# N-P-MOSFET_adapter.net
KiCad netlist of a schematic drawn in EAGLE
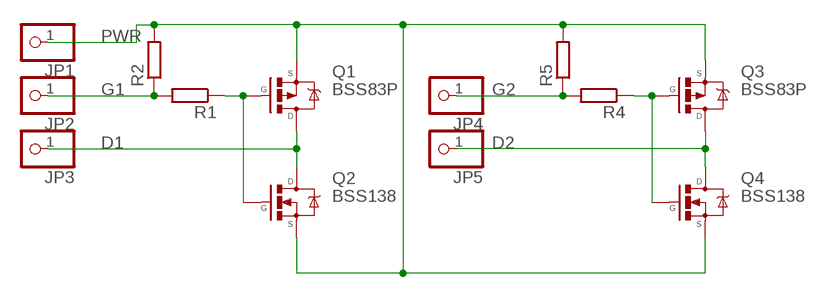
[diagram p0: schematic, sheet 1]

(export (version "E")
  (design (tool "Eeschema 10.0.6"))
  (components
    (comp (ref "JP1")
      (value "PINHD-1X1JUST_PIN")
      (footprint "eagle-import:1X01_BARE")
      (libsource (lib "eagle-import") (part "PINHD-1X1JUST_PIN"))
    )
    (comp (ref "JP2")
      (value "PINHD-1X1JUST_PIN")
      (footprint "eagle-import:1X01_BARE")
      (libsource (lib "eagle-import") (part "PINHD-1X1JUST_PIN"))
    )
    (comp (ref "JP3")
      (value "PINHD-1X1JUST_PIN")
      (footprint "eagle-import:1X01_BARE")
      (libsource (lib "eagle-import") (part "PINHD-1X1JUST_PIN"))
    )
    (comp (ref "JP4")
      (value "PINHD-1X1JUST_PIN")
      (footprint "eagle-import:1X01_BARE")
      (libsource (lib "eagle-import") (part "PINHD-1X1JUST_PIN"))
    )
    (comp (ref "JP5")
      (value "PINHD-1X1JUST_PIN")
      (footprint "eagle-import:1X01_BARE")
      (libsource (lib "eagle-import") (part "PINHD-1X1JUST_PIN"))
    )
    (comp (ref "Q1")
      (value "BSS83P")
      (footprint "eagle-import:SOT23")
      (libsource (lib "eagle-import") (part "BSS83P"))
    )
    (comp (ref "Q2")
      (value "BSS138")
      (footprint "eagle-import:SOT23")
      (libsource (lib "eagle-import") (part "BSS138"))
    )
    (comp (ref "Q3")
      (value "BSS83P")
      (footprint "eagle-import:SOT23")
      (libsource (lib "eagle-import") (part "BSS83P"))
    )
    (comp (ref "Q4")
      (value "BSS138")
      (footprint "eagle-import:SOT23")
      (libsource (lib "eagle-import") (part "BSS138"))
    )
    (comp (ref "R1")
      (value "R-EU_R0805")
      (footprint "eagle-import:R0805")
      (libsource (lib "eagle-import") (part "R-EU_R0805"))
    )
    (comp (ref "R2")
      (value "R-EU_R0805")
      (footprint "eagle-import:R0805")
      (libsource (lib "eagle-import") (part "R-EU_R0805"))
    )
    (comp (ref "R4")
      (value "R-EU_R0805")
      (footprint "eagle-import:R0805")
      (libsource (lib "eagle-import") (part "R-EU_R0805"))
    )
    (comp (ref "R5")
      (value "R-EU_R0805")
      (footprint "eagle-import:R0805")
      (libsource (lib "eagle-import") (part "R-EU_R0805"))
    )
  )
  (nets
    (net (code "1") (name "/D1") (class "Default")
      (node (ref "JP3") (pin "1") (pinfunction "1_1") (pintype "passive"))
      (node (ref "Q1") (pin "3") (pinfunction "D_3") (pintype "passive"))
      (node (ref "Q2") (pin "3") (pinfunction "D_3") (pintype "passive"))
    )
    (net (code "2") (name "/D2") (class "Default")
      (node (ref "JP5") (pin "1") (pinfunction "1_1") (pintype "passive"))
      (node (ref "Q3") (pin "3") (pinfunction "D_3") (pintype "passive"))
      (node (ref "Q4") (pin "3") (pinfunction "D_3") (pintype "passive"))
    )
    (net (code "3") (name "/G1") (class "Default")
      (node (ref "JP2") (pin "1") (pinfunction "1_1") (pintype "passive"))
      (node (ref "R1") (pin "2") (pinfunction "2_2") (pintype "passive"))
      (node (ref "R2") (pin "1") (pinfunction "1_1") (pintype "passive"))
    )
    (net (code "4") (name "/G2") (class "Default")
      (node (ref "JP4") (pin "1") (pinfunction "1_1") (pintype "passive"))
      (node (ref "R4") (pin "2") (pinfunction "2_2") (pintype "passive"))
      (node (ref "R5") (pin "1") (pinfunction "1_1") (pintype "passive"))
    )
    (net (code "5") (name "/PWR") (class "Default")
      (node (ref "JP1") (pin "1") (pinfunction "1_1") (pintype "passive"))
      (node (ref "Q1") (pin "2") (pinfunction "S_2") (pintype "passive"))
      (node (ref "Q2") (pin "2") (pinfunction "S_2") (pintype "passive"))
      (node (ref "Q3") (pin "2") (pinfunction "S_2") (pintype "passive"))
      (node (ref "Q4") (pin "2") (pinfunction "S_2") (pintype "passive"))
      (node (ref "R2") (pin "2") (pinfunction "2_2") (pintype "passive"))
      (node (ref "R5") (pin "2") (pinfunction "2_2") (pintype "passive"))
    )
    (net (code "6") (name "Net-(Q1-G)") (class "Default")
      (node (ref "Q1") (pin "1") (pinfunction "G_1") (pintype "passive"))
      (node (ref "Q2") (pin "1") (pinfunction "G_1") (pintype "passive"))
      (node (ref "R1") (pin "1") (pinfunction "1_1") (pintype "passive"))
    )
    (net (code "7") (name "Net-(Q3-G)") (class "Default")
      (node (ref "Q3") (pin "1") (pinfunction "G_1") (pintype "passive"))
      (node (ref "Q4") (pin "1") (pinfunction "G_1") (pintype "passive"))
      (node (ref "R4") (pin "1") (pinfunction "1_1") (pintype "passive"))
    )
  )
)
